# power_supply.net
KiCad netlist of a schematic drawn in Altium Designer
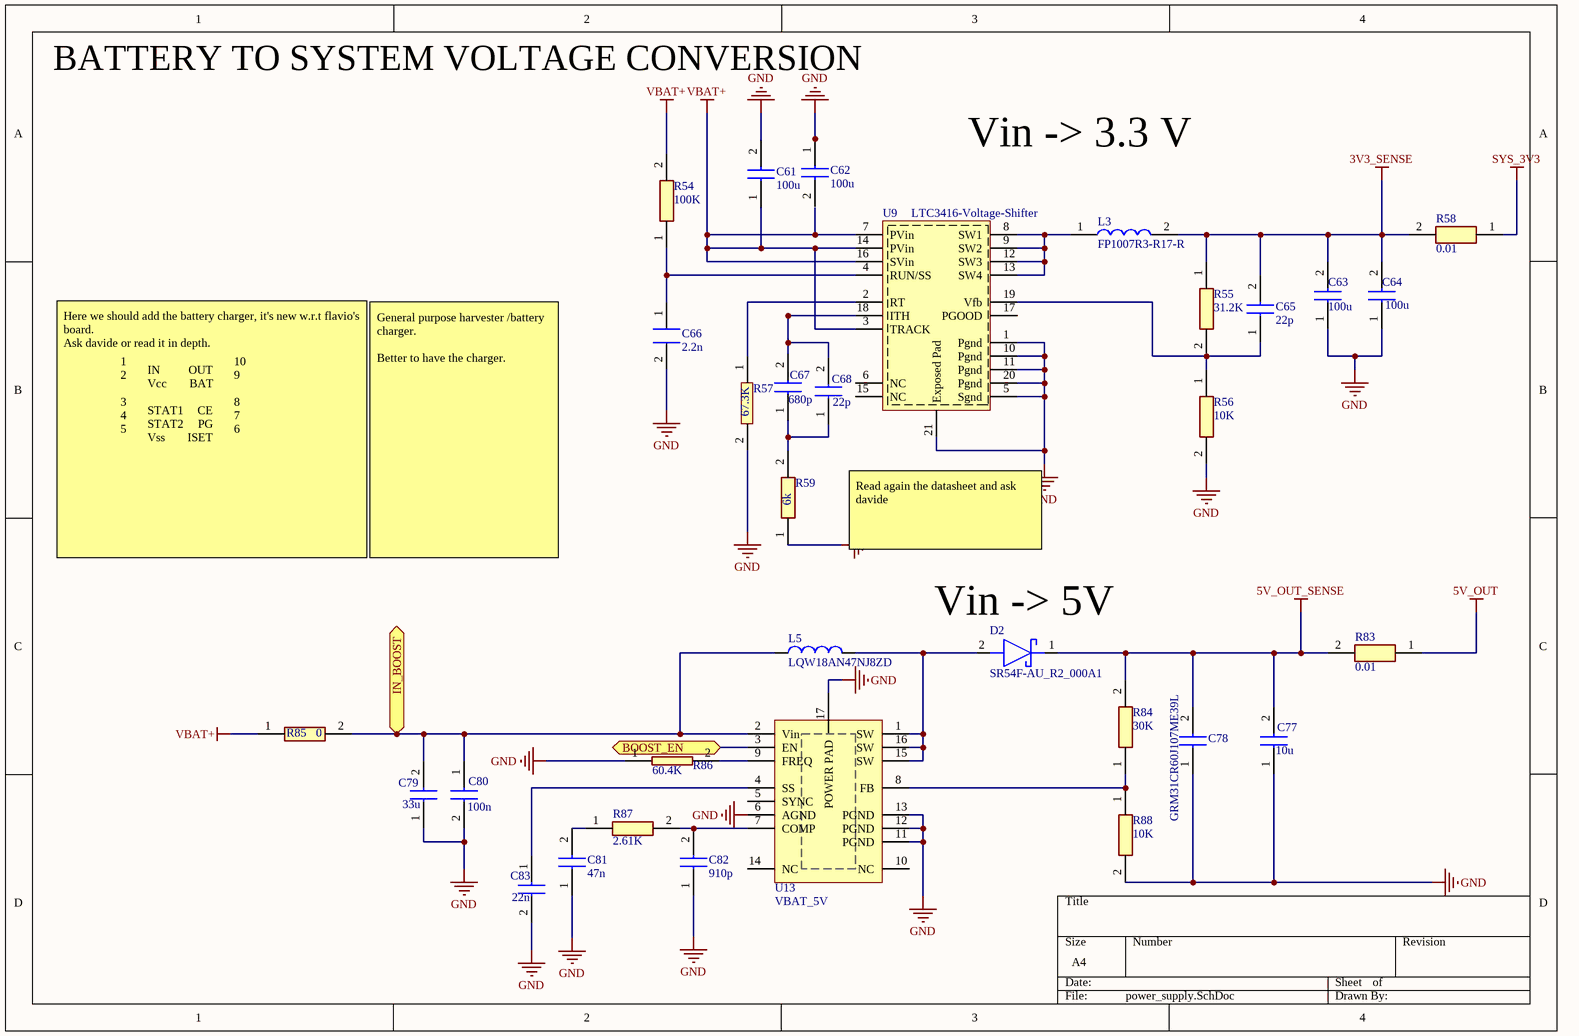
[diagram p0: power_supply.SchDoc]

(export (version "E")
  (design (tool "Eeschema 10.0.6"))
  (components
    (comp (ref "C61")
      (value "100u")
      (fields
        (field (name "MANUFACTURER") "TDK")
        (field (name "MANUFACTURER PART NUMBER") "C4532X5R0J107M280KA")
        (field (name "TOLERANCE") "20%")
      )
      (libsource (lib "shm_schem_lib") (part "C4532X5R0J107M280KA"))
    )
    (comp (ref "C62")
      (value "100u")
      (fields
        (field (name "MANUFACTURER") "TDK")
        (field (name "MANUFACTURER PART NUMBER") "C4532X5R0J107M280KA")
        (field (name "TOLERANCE") "20%")
      )
      (libsource (lib "shm_schem_lib") (part "C4532X5R0J107M280KA"))
    )
    (comp (ref "C63")
      (value "100u")
      (fields
        (field (name "MANUFACTURER") "TDK")
        (field (name "MANUFACTURER PART NUMBER") "C4532X5R0J107M280KA")
        (field (name "TOLERANCE") "20%")
      )
      (libsource (lib "shm_schem_lib") (part "C4532X5R0J107M280KA"))
    )
    (comp (ref "C64")
      (value "100u")
      (fields
        (field (name "MANUFACTURER") "TDK")
        (field (name "MANUFACTURER PART NUMBER") "C4532X5R0J107M280KA")
        (field (name "TOLERANCE") "20%")
      )
      (libsource (lib "shm_schem_lib") (part "C4532X5R0J107M280KA"))
    )
    (comp (ref "C65")
      (value "22p")
      (footprint "SamacSys:CAPC0603X33N")
      (description "Capacitor")
      (fields (field (name "MANUFACTURER_PART_NUMBER") "CBR02C220F9GAC"))
      (libsource (lib "*") (part "CBR02C220F9GAC"))
    )
    (comp (ref "C66")
      (value "2.2n")
      (description "Cap Cer 0603 2.2nF 200V X7R 4K 7\" Reel")
      (fields
        (field (name "MANUFACTURER") "KEMET")
        (field (name "MANUFACTURER PART NUMBER") "C0603C222K2RECAUTO")
      )
      (libsource (lib "shm_schem_lib") (part "C0603C222K2RECAUTO"))
    )
    (comp (ref "C67")
      (value "680p")
      (footprint "SamacSys:CAPC2012X140N")
      (description "Capacitor")
      (fields (field (name "MANUFACTURER_PART_NUMBER") "C0805C681JCTACAUTO"))
      (libsource (lib "*") (part "C0805C681JCTACAUTO"))
    )
    (comp (ref "C68")
      (value "22p")
      (footprint "SamacSys:CAPC0603X33N")
      (description "Capacitor")
      (fields (field (name "MANUFACTURER_PART_NUMBER") "CBR02C220F9GAC"))
      (libsource (lib "*") (part "CBR02C220F9GAC"))
    )
    (comp (ref "C77")
      (value "10u")
      (footprint "SamacSys:CAPC1608X100N")
      (description "Capacitor")
      (fields
        (field (name "MOUSER2 PART NUMBER") "963-LMK107BBJ106KALT")
        (field (name "MANUFACTURER_PART_NUMBER") "LMK107BBJ106KALT")
      )
      (libsource (lib "*") (part "LMK107BBJ106KALT"))
    )
    (comp (ref "C78")
      (value "GRM31CR60J107ME39L")
      (footprint "SamacSys:CAPC3216X180N")
      (description "Capacitor")
      (fields (field (name "MOUSER2 PART NUMBER") "81-GRM31CR60J107ME9L"))
      (libsource (lib "SamacSys") (part "GRM31CR60J107ME39L"))
    )
    (comp (ref "C79")
      (value "33u")
      (footprint "SamacSys:C2012_Commercial")
      (description "Capacitor")
      (fields (field (name "MANUFACTURER_PART_NUMBER") "C2012X5R1A336M125AC"))
      (libsource (lib "*") (part "C2012X5R1A336M125AC"))
    )
    (comp (ref "C80")
      (value "100n")
      (footprint "SamacSys:CAPC1608X87N")
      (description "Capacitor")
      (fields (field (name "MANUFACTURER_PART_NUMBER") "885012206071"))
      (libsource (lib "*") (part "885012206071"))
    )
    (comp (ref "C81")
      (value "47n")
      (footprint "SamacSys:CAPC2012X90N")
      (description "Capacitor")
      (fields (field (name "MANUFACTURER_PART_NUMBER") "885012207070"))
      (libsource (lib "*") (part "885012207070"))
    )
    (comp (ref "C82")
      (value "910p")
      (description "Cap Ceramic 910pF 50V X7R 10% SMD 0805 125°C T/R")
      (fields
        (field (name "MANUFACTURER") "Kyocera AVX")
        (field (name "MANUFACTURER PART NUMBER") "08055C911KAT2A")
      )
      (libsource (lib "shm_schem_lib") (part "08055C911KAT2A"))
    )
    (comp (ref "C83")
      (value "22n")
      (footprint "SamacSys:CAPC2012X90N")
      (description "Capacitor")
      (fields
        (field (name "MOUSER2 PART NUMBER") "710-885012207094")
        (field (name "MANUFACTURER_PART_NUMBER") "885012207094")
      )
      (libsource (lib "*") (part "885012207094"))
    )
    (comp (ref "D2")
      (value "SR54F-AU_R2_000A1")
      (footprint "SamacSys:SODFL5336X110N")
      (description "Schottky Diode")
      (libsource (lib "*") (part "SR54F-AU_R2_000A1"))
    )
    (comp (ref "L3")
      (value "FP1007R3-R17-R")
      (description "General Purpose Inductor, 0.17uH, 10%, 1 Element, Ferrite-Core, SMD, 4131")
      (fields (field (name "MANUFACTURER") "Eaton Bussmann") (field (name "TOLERANCE") "10%"))
      (libsource (lib "shm_schem_lib") (part "FP1007R3-R17-R"))
    )
    (comp (ref "L5")
      (value "LQW18AN47NJ8ZD")
      (footprint "INDC1609X100N")
      (description "FIXED IND 47NH 830MA 230 MOHM")
      (libsource (lib "LQW18AN47NJ8ZD") (part "LQW18AN47NJ8ZD"))
    )
    (comp (ref "R54")
      (value "100K")
      (footprint "SamacSys:RESC2012X60N")
      (description "Resistor")
      (fields (field (name "MANUFACTURER_PART_NUMBER") "CHV0805AFX-1003ELF"))
      (libsource (lib "*") (part "CHV0805AFX-1003ELF"))
    )
    (comp (ref "R55")
      (value "31.2K")
      (footprint "SamacSys:RESC1005X37N")
      (description "Resistor")
      (fields (field (name "MANUFACTURER_PART_NUMBER") "MCS04020D3122BE100"))
      (libsource (lib "*") (part "MCS04020D3122BE100"))
    )
    (comp (ref "R56")
      (value "10K")
      (footprint "SamacSys:ERJ3EK_(0603)")
      (description "Resistor")
      (fields
        (field (name "MOUSER2 PART NUMBER") "667-ERJ-3EKF1002V")
        (field (name "MANUFACTURER_PART_NUMBER") "ERJ-3EKF1002V")
      )
      (libsource (lib "*") (part "ERJ-3EKF1002V"))
    )
    (comp (ref "R57")
      (value "67.3K")
      (description "Res 67.3K Ohm 0.1% 1/10W 0805")
      (fields
        (field (name "MANUFACTURER") "KOA Speer")
        (field (name "MANUFACTURER PART NUMBER") "RN732ATTD6732B25")
      )
      (libsource (lib "shm_schem_lib") (part "RN732ATTD6732B25"))
    )
    (comp (ref "R58")
      (value "0.01")
      (description "Res Metal Alloy 1206 0.01 Ohm 0.5% 0.5W(1/2W) ±50ppm/C Pad SMD T/R")
      (fields (field (name "MANUFACTURER") "Ohmite") (field (name "MANUFACTURER PART NUMBER") "LVK12R010DER"))
      (libsource (lib "shm_schem_lib") (part "LVK12R010DER (2)"))
    )
    (comp (ref "R59")
      (value "6k")
      (footprint "SamacSys:ERA6A_(0805)")
      (description "Resistor")
      (fields (field (name "MANUFACTURER_PART_NUMBER") "ERA-6ARB6041V"))
      (libsource (lib "*") (part "ERA-6ARB6041V"))
    )
    (comp (ref "R83")
      (value "0.01")
      (description "Res Metal Alloy 1206 0.01 Ohm 0.5% 0.5W(1/2W) ±50ppm/C Pad SMD T/R")
      (fields (field (name "MANUFACTURER") "Ohmite") (field (name "MANUFACTURER PART NUMBER") "LVK12R010DER"))
      (libsource (lib "shm_schem_lib") (part "LVK12R010DER (2)"))
    )
    (comp (ref "R84")
      (value "30K")
      (footprint "SamacSys:RESC1608X55N")
      (description "Resistor")
      (fields
        (field (name "MOUSER2 PART NUMBER") "71-CRCW060330K0FKEAC")
        (field (name "MANUFACTURER_PART_NUMBER") "CRCW060330K0FKEAC")
      )
      (libsource (lib "*") (part "CRCW060330K0FKEAC"))
    )
    (comp (ref "R85")
      (value "0")
      (footprint "SamacSys:RESC1608X55N")
      (description "Resistor")
      (fields (field (name "MANUFACTURER_PART_NUMBER") "RC0603FR-070RL"))
      (libsource (lib "*") (part "RC0603FR-070RL"))
    )
    (comp (ref "R86")
      (value "60.4K")
      (description "Res Thick Film 0603 60.4K Ohm 1% 1/10W ±100ppm/°C Molded SMD Paper T/R")
      (fields
        (field (name "MANUFACTURER") "Vishay")
        (field (name "MANUFACTURER PART NUMBER") "CRCW060360K4FKEAC")
      )
      (libsource (lib "shm_schem_lib") (part "CRCW060360K4FKEAC"))
    )
    (comp (ref "R87")
      (value "2.61K")
      (footprint "SamacSys:RESC1608X50N")
      (description "Resistor")
      (fields (field (name "MANUFACTURER_PART_NUMBER") "CRCW06032K61FKEA"))
      (libsource (lib "*") (part "CRCW06032K61FKEA"))
    )
    (comp (ref "R88")
      (value "10K")
      (footprint "SamacSys:ERJ3EK_(0603)")
      (description "Resistor")
      (fields
        (field (name "MOUSER2 PART NUMBER") "667-ERJ-3EKF1002V")
        (field (name "MANUFACTURER_PART_NUMBER") "ERJ-3EKF1002V")
      )
      (libsource (lib "*") (part "ERJ-3EKF1002V"))
    )
    (comp (ref "U8")
      (value "TI_Battery_Charger")
      (fields
        (field (name "MANUFACTURER") "Texas Instruments")
        (field (name "MANUFACTURER PART NUMBER") "BQ24012DRCR")
      )
      (libsource (lib "shm_schem_lib") (part "BQ24012DRCR"))
    )
    (comp (ref "U9")
      (value "LTC3416-Voltage-Shifter")
      (description "Conv DC-DC 2.25V to 5.5V Synchronous Step Down Single-Out 0.8V to 5V 4A Automotive 20-Pin TSSOP EP")
      (fields
        (field (name "MANUFACTURER") "Analog Devices")
        (field (name "MANUFACTURER PART NUMBER") "LTC3416EFE#PBF")
      )
      (libsource (lib "shm_schem_lib") (part "LTC3416EFE#PBF"))
    )
    (comp (ref "U13")
      (value "VBAT_5V")
      (footprint "QFN50P300X300X80-17N-D")
      (description "Conv DC-DC 2.9V to 38V Step Up Single-Out 2.9V to 38V 5A Automotive 16-Pin WQFN EP T/R")
      (fields
        (field (name "MANUFACTURER") "Texas Instruments")
        (field (name "MANUFACTURER PART NUMBER") "TPS55340QRTERQ1")
      )
      (libsource (lib "shm_schem_lib") (part "TPS55340QRTERQ1"))
    )
  )
  (nets
    (net (code "1") (name "/BOOST_EN") (class "Default")
      (node (ref "U13") (pin "3") (pinfunction "EN_3") (pintype "passive"))
    )
    (net (code "2") (name "/IN_BOOST") (class "Default")
      (node (ref "C79") (pin "2") (pinfunction "2_2") (pintype "passive"))
      (node (ref "C80") (pin "1") (pinfunction "1_1") (pintype "passive"))
      (node (ref "L5") (pin "1") (pinfunction "1_1") (pintype "passive"))
      (node (ref "R85") (pin "2") (pinfunction "2_2") (pintype "passive"))
      (node (ref "U13") (pin "2") (pinfunction "Vin_2") (pintype "passive"))
    )
    (net (code "3") (name "3V3_SENSE") (class "Default")
      (node (ref "C63") (pin "2") (pinfunction "2_2") (pintype "passive"))
      (node (ref "C64") (pin "2") (pinfunction "2_2") (pintype "passive"))
      (node (ref "C65") (pin "2") (pinfunction "2_2") (pintype "passive"))
      (node (ref "L3") (pin "2") (pinfunction "2_2") (pintype "passive"))
      (node (ref "R55") (pin "1") (pinfunction "1_1") (pintype "passive"))
      (node (ref "R58") (pin "2") (pinfunction "2_2") (pintype "passive"))
    )
    (net (code "4") (name "5V_OUT") (class "Default")
      (node (ref "R83") (pin "1") (pinfunction "1_1") (pintype "passive"))
    )
    (net (code "5") (name "5V_OUT_SENSE") (class "Default")
      (node (ref "C77") (pin "2") (pinfunction "2_2") (pintype "passive"))
      (node (ref "C78") (pin "2") (pinfunction "2_2") (pintype "passive"))
      (node (ref "D2") (pin "1") (pinfunction "K_1") (pintype "passive"))
      (node (ref "R83") (pin "2") (pinfunction "2_2") (pintype "passive"))
      (node (ref "R84") (pin "2") (pinfunction "2_2") (pintype "passive"))
    )
    (net (code "6") (name "GND") (class "Default")
      (node (ref "C61") (pin "2") (pinfunction "2_2") (pintype "passive"))
      (node (ref "C62") (pin "1") (pinfunction "1_1") (pintype "passive"))
      (node (ref "C63") (pin "1") (pinfunction "1_1") (pintype "passive"))
      (node (ref "C64") (pin "1") (pinfunction "1_1") (pintype "passive"))
      (node (ref "C66") (pin "2") (pinfunction "51_2") (pintype "passive"))
      (node (ref "C77") (pin "1") (pinfunction "1_1") (pintype "passive"))
      (node (ref "C78") (pin "1") (pinfunction "1_1") (pintype "passive"))
      (node (ref "C79") (pin "1") (pinfunction "1_1") (pintype "passive"))
      (node (ref "C80") (pin "2") (pinfunction "2_2") (pintype "passive"))
      (node (ref "C81") (pin "1") (pinfunction "1_1") (pintype "passive"))
      (node (ref "C82") (pin "1") (pinfunction "18_1") (pintype "passive"))
      (node (ref "C83") (pin "2") (pinfunction "2_2") (pintype "passive"))
      (node (ref "R56") (pin "2") (pinfunction "2_2") (pintype "passive"))
      (node (ref "R57") (pin "2") (pinfunction "2_2") (pintype "passive"))
      (node (ref "R59") (pin "1") (pinfunction "1_1") (pintype "passive"))
      (node (ref "R86") (pin "1") (pinfunction "1_1") (pintype "passive"))
      (node (ref "R88") (pin "2") (pinfunction "2_2") (pintype "passive"))
      (node (ref "U13") (pin "11") (pinfunction "PGND_11") (pintype "passive"))
      (node (ref "U13") (pin "12") (pinfunction "PGND_12") (pintype "passive"))
      (node (ref "U13") (pin "13") (pinfunction "PGND_13") (pintype "passive"))
      (node (ref "U13") (pin "17") (pinfunction "POWER_PAD_17") (pintype "passive"))
      (node (ref "U13") (pin "6") (pinfunction "AGND_6") (pintype "passive"))
      (node (ref "U9") (pin "1") (pinfunction "Pgnd_1") (pintype "passive"))
      (node (ref "U9") (pin "10") (pinfunction "Pgnd_10") (pintype "passive"))
      (node (ref "U9") (pin "11") (pinfunction "Pgnd_11") (pintype "passive"))
      (node (ref "U9") (pin "20") (pinfunction "Pgnd_20") (pintype "passive"))
      (node (ref "U9") (pin "21") (pinfunction "Exposed_Pad_21") (pintype "passive"))
      (node (ref "U9") (pin "5") (pinfunction "Sgnd_5") (pintype "passive"))
    )
    (net (code "7") (name "Net-(C67-Pad1)") (class "Default")
      (node (ref "C67") (pin "1") (pinfunction "1_1") (pintype "passive"))
      (node (ref "C68") (pin "1") (pinfunction "1_1") (pintype "passive"))
      (node (ref "R59") (pin "2") (pinfunction "2_2") (pintype "passive"))
    )
    (net (code "8") (name "Net-(C81-Pad2)") (class "Default")
      (node (ref "C81") (pin "2") (pinfunction "2_2") (pintype "passive"))
      (node (ref "R87") (pin "1") (pinfunction "1_1") (pintype "passive"))
    )
    (net (code "9") (name "Net-(C82-19)") (class "Default")
      (node (ref "C82") (pin "2") (pinfunction "19_2") (pintype "passive"))
      (node (ref "R87") (pin "2") (pinfunction "2_2") (pintype "passive"))
      (node (ref "U13") (pin "7") (pinfunction "COMP_7") (pintype "passive"))
    )
    (net (code "10") (name "Net-(D2-A)") (class "Default")
      (node (ref "D2") (pin "2") (pinfunction "A_2") (pintype "passive"))
      (node (ref "L5") (pin "2") (pinfunction "2_2") (pintype "passive"))
      (node (ref "U13") (pin "1") (pinfunction "SW_1") (pintype "passive"))
      (node (ref "U13") (pin "15") (pinfunction "SW_15") (pintype "passive"))
      (node (ref "U13") (pin "16") (pinfunction "SW_16") (pintype "passive"))
    )
    (net (code "11") (name "Net-(U9-ITH)") (class "Default")
      (node (ref "C67") (pin "2") (pinfunction "2_2") (pintype "passive"))
      (node (ref "C68") (pin "2") (pinfunction "2_2") (pintype "passive"))
      (node (ref "U9") (pin "18") (pinfunction "ITH_18") (pintype "passive"))
    )
    (net (code "12") (name "Net-(U9-RT)") (class "Default")
      (node (ref "R57") (pin "1") (pinfunction "1_1") (pintype "passive"))
      (node (ref "U9") (pin "2") (pinfunction "RT_2") (pintype "passive"))
    )
    (net (code "13") (name "Net-(U9-RUN{slash}SS)") (class "Default")
      (node (ref "C66") (pin "1") (pinfunction "1_1") (pintype "passive"))
      (node (ref "R54") (pin "1") (pinfunction "1_1") (pintype "passive"))
      (node (ref "U9") (pin "4") (pinfunction "RUN/SS_4") (pintype "passive"))
    )
    (net (code "14") (name "Net-(U9-SW1)") (class "Default")
      (node (ref "L3") (pin "1") (pinfunction "1_1") (pintype "passive"))
      (node (ref "U9") (pin "12") (pinfunction "SW3_12") (pintype "passive"))
      (node (ref "U9") (pin "13") (pinfunction "SW4_13") (pintype "passive"))
      (node (ref "U9") (pin "8") (pinfunction "SW1_8") (pintype "passive"))
      (node (ref "U9") (pin "9") (pinfunction "SW2_9") (pintype "passive"))
    )
    (net (code "15") (name "Net-(U9-Vfb)") (class "Default")
      (node (ref "C65") (pin "1") (pinfunction "1_1") (pintype "passive"))
      (node (ref "R55") (pin "2") (pinfunction "2_2") (pintype "passive"))
      (node (ref "R56") (pin "1") (pinfunction "1_1") (pintype "passive"))
      (node (ref "U9") (pin "19") (pinfunction "Vfb_19") (pintype "passive"))
    )
    (net (code "16") (name "Net-(U13-FB)") (class "Default")
      (node (ref "R84") (pin "1") (pinfunction "1_1") (pintype "passive"))
      (node (ref "R88") (pin "1") (pinfunction "1_1") (pintype "passive"))
      (node (ref "U13") (pin "8") (pinfunction "FB_8") (pintype "passive"))
    )
    (net (code "17") (name "Net-(U13-FREQ)") (class "Default")
      (node (ref "R86") (pin "2") (pinfunction "2_2") (pintype "passive"))
      (node (ref "U13") (pin "9") (pinfunction "FREQ_9") (pintype "passive"))
    )
    (net (code "18") (name "Net-(U13-SS)") (class "Default")
      (node (ref "C83") (pin "1") (pinfunction "1_1") (pintype "passive"))
      (node (ref "U13") (pin "4") (pinfunction "SS_4") (pintype "passive"))
    )
    (net (code "19") (name "SYS_3V3") (class "Default")
      (node (ref "R58") (pin "1") (pinfunction "1_1") (pintype "passive"))
    )
    (net (code "20") (name "VBAT+") (class "Default")
      (node (ref "C61") (pin "1") (pinfunction "1_1") (pintype "passive"))
      (node (ref "R54") (pin "2") (pinfunction "2_2") (pintype "passive"))
      (node (ref "R85") (pin "1") (pinfunction "1_1") (pintype "passive"))
      (node (ref "U9") (pin "14") (pinfunction "PVin_14") (pintype "passive"))
      (node (ref "U9") (pin "16") (pinfunction "SVin_16") (pintype "passive"))
      (node (ref "U9") (pin "3") (pinfunction "TRACK_3") (pintype "passive"))
      (node (ref "U9") (pin "7") (pinfunction "PVin_7") (pintype "passive"))
    )
    (net (code "21") (name "unconnected-(C62-Pad2)") (class "Default")
      (node (ref "C62") (pin "2") (pinfunction "2_2") (pintype "passive"))
    )
    (net (code "22") (name "unconnected-(U8-BAT-Pad9)") (class "Default")
      (node (ref "U8") (pin "9") (pinfunction "BAT_9") (pintype "passive"))
    )
    (net (code "23") (name "unconnected-(U8-CE-Pad8)") (class "Default")
      (node (ref "U8") (pin "8") (pinfunction "CE_8") (pintype "passive"))
    )
    (net (code "24") (name "unconnected-(U8-IN-Pad1)") (class "Default")
      (node (ref "U8") (pin "1") (pinfunction "IN_1") (pintype "passive"))
    )
    (net (code "25") (name "unconnected-(U8-ISET-Pad6)") (class "Default")
      (node (ref "U8") (pin "6") (pinfunction "ISET_6") (pintype "passive"))
    )
    (net (code "26") (name "unconnected-(U8-OUT-Pad10)") (class "Default")
      (node (ref "U8") (pin "10") (pinfunction "OUT_10") (pintype "passive"))
    )
    (net (code "27") (name "unconnected-(U8-PG-Pad7)") (class "Default")
      (node (ref "U8") (pin "7") (pinfunction "PG_7") (pintype "passive"))
    )
    (net (code "28") (name "unconnected-(U8-STAT1-Pad3)") (class "Default")
      (node (ref "U8") (pin "3") (pinfunction "STAT1_3") (pintype "passive"))
    )
    (net (code "29") (name "unconnected-(U8-STAT2-Pad4)") (class "Default")
      (node (ref "U8") (pin "4") (pinfunction "STAT2_4") (pintype "passive"))
    )
    (net (code "30") (name "unconnected-(U8-Vcc-Pad2)") (class "Default")
      (node (ref "U8") (pin "2") (pinfunction "Vcc_2") (pintype "passive"))
    )
    (net (code "31") (name "unconnected-(U8-Vss-Pad5)") (class "Default")
      (node (ref "U8") (pin "5") (pinfunction "Vss_5") (pintype "passive"))
    )
    (net (code "32") (name "unconnected-(U9-NC-Pad6)") (class "Default")
      (node (ref "U9") (pin "6") (pinfunction "NC_6") (pintype "passive"))
    )
    (net (code "33") (name "unconnected-(U9-NC-Pad15)") (class "Default")
      (node (ref "U9") (pin "15") (pinfunction "NC_15") (pintype "passive"))
    )
    (net (code "34") (name "unconnected-(U9-PGOOD-Pad17)") (class "Default")
      (node (ref "U9") (pin "17") (pinfunction "PGOOD_17") (pintype "passive"))
    )
    (net (code "35") (name "unconnected-(U13-NC-Pad10)") (class "Default")
      (node (ref "U13") (pin "10") (pinfunction "NC_10") (pintype "passive"))
    )
    (net (code "36") (name "unconnected-(U13-NC-Pad14)") (class "Default")
      (node (ref "U13") (pin "14") (pinfunction "NC_14") (pintype "passive"))
    )
    (net (code "37") (name "unconnected-(U13-SYNC-Pad5)") (class "Default")
      (node (ref "U13") (pin "5") (pinfunction "SYNC_5") (pintype "passive"))
    )
  )
)
